# TPS54302.net
KiCad netlist of a schematic drawn in EAGLE
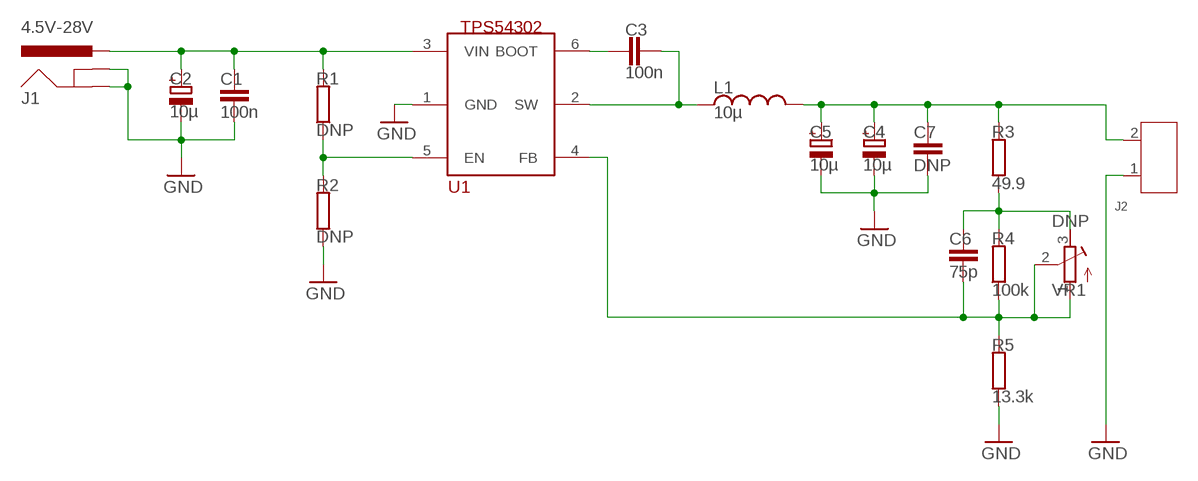
[diagram p0: schematic, sheet 1]

(export (version "E")
  (design (tool "Eeschema 10.0.6"))
  (components
    (comp (ref "C1")
      (value "100n")
      (footprint "eagle-import:C0603K")
      (libsource (lib "eagle-import") (part "C-EUC0603K"))
    )
    (comp (ref "C2")
      (value "10µ")
      (footprint "eagle-import:153CLV-0605")
      (libsource (lib "eagle-import") (part "CPOL-EU153CLV-0605"))
    )
    (comp (ref "C3")
      (value "100n")
      (footprint "eagle-import:C0603K")
      (libsource (lib "eagle-import") (part "C-EUC0603K"))
    )
    (comp (ref "C4")
      (value "10µ")
      (footprint "eagle-import:153CLV-0605")
      (libsource (lib "eagle-import") (part "CPOL-EU153CLV-0605"))
    )
    (comp (ref "C5")
      (value "10µ")
      (footprint "eagle-import:153CLV-0605")
      (libsource (lib "eagle-import") (part "CPOL-EU153CLV-0605"))
    )
    (comp (ref "C6")
      (value "75p")
      (footprint "eagle-import:C0603K")
      (libsource (lib "eagle-import") (part "C-EUC0603K"))
    )
    (comp (ref "C7")
      (value "DNP")
      (footprint "eagle-import:C0603K")
      (libsource (lib "eagle-import") (part "C-EUC0603K"))
    )
    (comp (ref "J1")
      (value "4.5V-28V")
      (footprint "eagle-import:POWER_JACK_COMBO")
      (libsource (lib "eagle-import") (part "POWER_JACKPTH_SMD_COMBO"))
    )
    (comp (ref "J2")
      (value "SCREW-TERMINAL-GREEN(2P-5.0)")
      (footprint "eagle-import:H2-5.0-10.5X8.0MM")
      (libsource (lib "eagle-import") (part "SCREW-TERMINAL-GREEN(2P-5.0)"))
    )
    (comp (ref "L1")
      (value "10µ")
      (footprint "eagle-import:INDDFN800X800X420-2N")
      (libsource (lib "eagle-import") (part "INDUCTOR8080"))
    )
    (comp (ref "R1")
      (value "DNP")
      (footprint "eagle-import:R0603")
      (libsource (lib "eagle-import") (part "R-EU_R0603"))
    )
    (comp (ref "R2")
      (value "DNP")
      (footprint "eagle-import:R0603")
      (libsource (lib "eagle-import") (part "R-EU_R0603"))
    )
    (comp (ref "R3")
      (value "49.9")
      (footprint "eagle-import:R0603")
      (libsource (lib "eagle-import") (part "R-EU_R0603"))
    )
    (comp (ref "R4")
      (value "100k")
      (footprint "eagle-import:R0603")
      (libsource (lib "eagle-import") (part "R-EU_R0603"))
    )
    (comp (ref "R5")
      (value "13.3k")
      (footprint "eagle-import:R0603")
      (libsource (lib "eagle-import") (part "R-EU_R0603"))
    )
    (comp (ref "U1")
      (value "TPS54302")
      (footprint "eagle-import:SOT95P280X110-6N")
      (libsource (lib "eagle-import") (part "TPS54302"))
    )
    (comp (ref "VR1")
      (value "DNP")
      (footprint "eagle-import:RTRIM64W")
      (libsource (lib "eagle-import") (part "R-TRIMM64W"))
    )
  )
  (nets
    (net (code "1") (name "GND") (class "Default")
      (node (ref "C1") (pin "2") (pinfunction "2_2") (pintype "passive"))
      (node (ref "C2") (pin "-") (pinfunction "-_-") (pintype "passive"))
      (node (ref "C4") (pin "-") (pinfunction "-_-") (pintype "passive"))
      (node (ref "C5") (pin "-") (pinfunction "-_-") (pintype "passive"))
      (node (ref "C7") (pin "2") (pinfunction "2_2") (pintype "passive"))
      (node (ref "J1") (pin "GND") (pinfunction "GNDBREAK_GND") (pintype "bidirectional"))
      (node (ref "J1") (pin "GND@1") (pinfunction "GND_GND@1") (pintype "bidirectional"))
      (node (ref "J1") (pin "GND@3") (pinfunction "GND_GND@3") (pintype "bidirectional"))
      (node (ref "J1") (pin "GND@4") (pinfunction "GND_GND@4") (pintype "bidirectional"))
      (node (ref "J2") (pin "1") (pinfunction "1_1") (pintype "bidirectional"))
      (node (ref "R2") (pin "1") (pinfunction "1_1") (pintype "passive"))
      (node (ref "R5") (pin "1") (pinfunction "1_1") (pintype "passive"))
      (node (ref "U1") (pin "1") (pinfunction "GND_1") (pintype "bidirectional"))
    )
    (net (code "2") (name "Net-(C4-Pad+)") (class "Default")
      (node (ref "C4") (pin "+") (pinfunction "+_+") (pintype "passive"))
      (node (ref "C5") (pin "+") (pinfunction "+_+") (pintype "passive"))
      (node (ref "C7") (pin "1") (pinfunction "1_1") (pintype "passive"))
      (node (ref "J2") (pin "2") (pinfunction "2_2") (pintype "bidirectional"))
      (node (ref "L1") (pin "2") (pinfunction "2_2") (pintype "passive"))
      (node (ref "R3") (pin "2") (pinfunction "2_2") (pintype "passive"))
    )
    (net (code "3") (name "Net-(U1-BOOT)") (class "Default")
      (node (ref "C3") (pin "1") (pinfunction "1_1") (pintype "passive"))
      (node (ref "U1") (pin "6") (pinfunction "BOOT_6") (pintype "bidirectional"))
    )
    (net (code "4") (name "Net-(U1-EN)") (class "Default")
      (node (ref "R1") (pin "1") (pinfunction "1_1") (pintype "passive"))
      (node (ref "R2") (pin "2") (pinfunction "2_2") (pintype "passive"))
      (node (ref "U1") (pin "5") (pinfunction "EN_5") (pintype "bidirectional"))
    )
    (net (code "5") (name "Net-(U1-FB)") (class "Default")
      (node (ref "C6") (pin "1") (pinfunction "1_1") (pintype "passive"))
      (node (ref "R4") (pin "1") (pinfunction "1_1") (pintype "passive"))
      (node (ref "R5") (pin "2") (pinfunction "2_2") (pintype "passive"))
      (node (ref "U1") (pin "4") (pinfunction "FB_4") (pintype "bidirectional"))
      (node (ref "VR1") (pin "1") (pinfunction "A_1") (pintype "passive"))
      (node (ref "VR1") (pin "2") (pinfunction "S_2") (pintype "passive"))
    )
    (net (code "6") (name "Net-(U1-SW)") (class "Default")
      (node (ref "C3") (pin "2") (pinfunction "2_2") (pintype "passive"))
      (node (ref "L1") (pin "1") (pinfunction "1_1") (pintype "passive"))
      (node (ref "U1") (pin "2") (pinfunction "SW_2") (pintype "bidirectional"))
    )
    (net (code "7") (name "Net-(U1-VIN)") (class "Default")
      (node (ref "C1") (pin "1") (pinfunction "1_1") (pintype "passive"))
      (node (ref "C2") (pin "+") (pinfunction "+_+") (pintype "passive"))
      (node (ref "J1") (pin "POWER") (pinfunction "PWR_POWER") (pintype "bidirectional"))
      (node (ref "J1") (pin "POWER@1") (pinfunction "PWR_POWER@1") (pintype "bidirectional"))
      (node (ref "J1") (pin "POWER@2") (pinfunction "PWR_POWER@2") (pintype "bidirectional"))
      (node (ref "R1") (pin "2") (pinfunction "2_2") (pintype "passive"))
      (node (ref "U1") (pin "3") (pinfunction "VIN_3") (pintype "bidirectional"))
    )
    (net (code "8") (name "Net-(VR1-E)") (class "Default")
      (node (ref "C6") (pin "2") (pinfunction "2_2") (pintype "passive"))
      (node (ref "R3") (pin "1") (pinfunction "1_1") (pintype "passive"))
      (node (ref "R4") (pin "2") (pinfunction "2_2") (pintype "passive"))
      (node (ref "VR1") (pin "3") (pinfunction "E_3") (pintype "passive"))
    )
  )
)
